# neojoint1-090.net
KiCad netlist of a schematic drawn in EAGLE
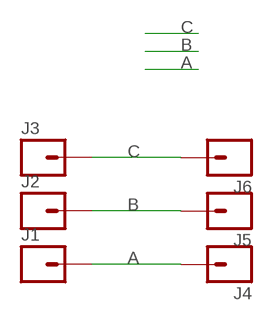
[diagram p0: schematic, sheet 1]

(export (version "E")
  (design (tool "Eeschema 10.0.6"))
  (components
    (comp (ref "J1")
      (value "M01SMD-4.5X1.5")
      (footprint "eagle-import:PAD-1.5X4.5")
      (libsource (lib "eagle-import") (part "M01SMD-4.5X1.5"))
    )
    (comp (ref "J2")
      (value "M01SMD-4.5X1.5")
      (footprint "eagle-import:PAD-1.5X4.5")
      (libsource (lib "eagle-import") (part "M01SMD-4.5X1.5"))
    )
    (comp (ref "J3")
      (value "M01SMD-4.5X1.5")
      (footprint "eagle-import:PAD-1.5X4.5")
      (libsource (lib "eagle-import") (part "M01SMD-4.5X1.5"))
    )
    (comp (ref "J4")
      (value "M01SMD-4.5X1.5")
      (footprint "eagle-import:PAD-1.5X4.5")
      (libsource (lib "eagle-import") (part "M01SMD-4.5X1.5"))
    )
    (comp (ref "J5")
      (value "M01SMD-4.5X1.5")
      (footprint "eagle-import:PAD-1.5X4.5")
      (libsource (lib "eagle-import") (part "M01SMD-4.5X1.5"))
    )
    (comp (ref "J6")
      (value "M01SMD-4.5X1.5")
      (footprint "eagle-import:PAD-1.5X4.5")
      (libsource (lib "eagle-import") (part "M01SMD-4.5X1.5"))
    )
  )
  (nets
    (net (code "1") (name "/A") (class "Default")
      (node (ref "J1") (pin "P$1") (pinfunction "1_P$1") (pintype "passive"))
      (node (ref "J4") (pin "P$1") (pinfunction "1_P$1") (pintype "passive"))
    )
    (net (code "2") (name "/B") (class "Default")
      (node (ref "J2") (pin "P$1") (pinfunction "1_P$1") (pintype "passive"))
      (node (ref "J5") (pin "P$1") (pinfunction "1_P$1") (pintype "passive"))
    )
    (net (code "3") (name "/C") (class "Default")
      (node (ref "J3") (pin "P$1") (pinfunction "1_P$1") (pintype "passive"))
      (node (ref "J6") (pin "P$1") (pinfunction "1_P$1") (pintype "passive"))
    )
  )
)
